# PSU_v1.net
KiCad netlist of a schematic drawn in EAGLE
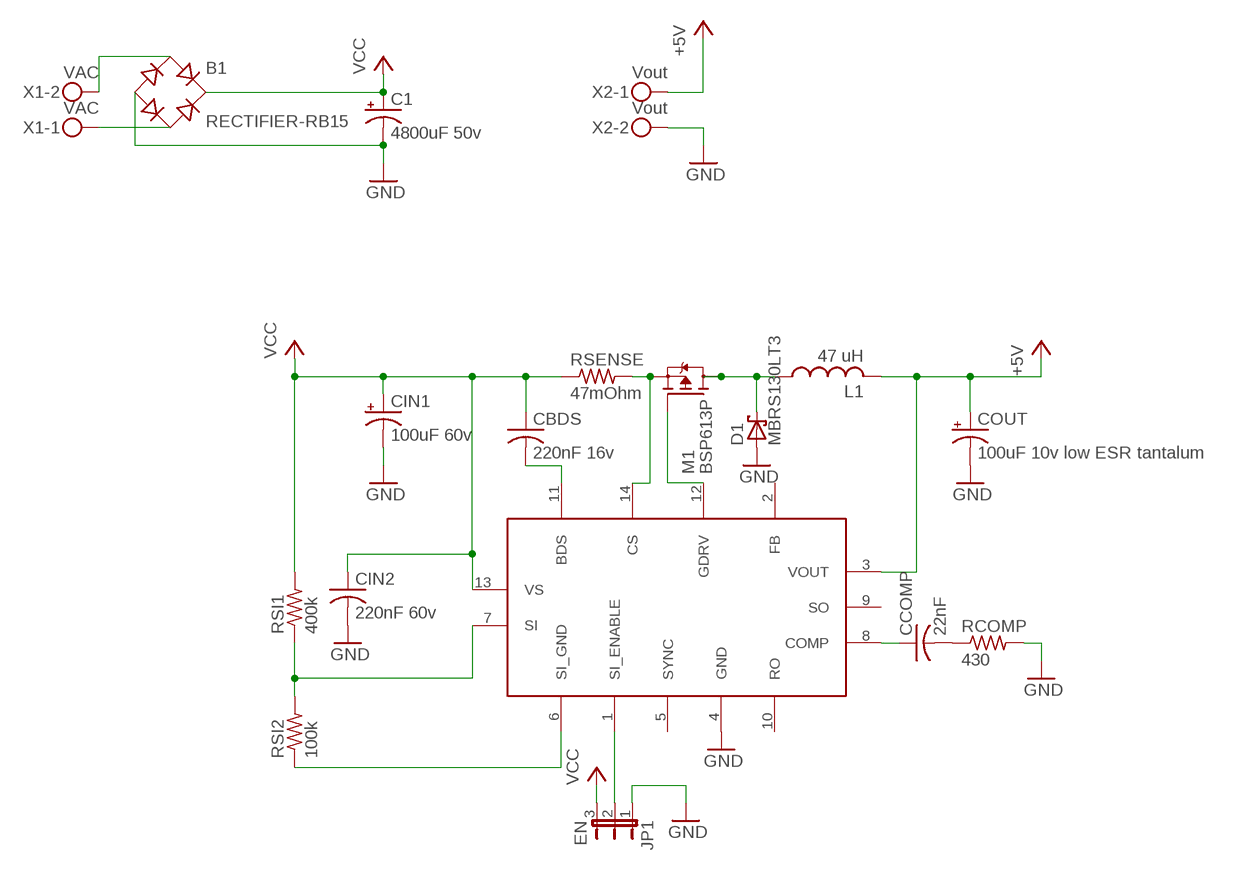
[diagram p0: schematic, sheet 1]

(export (version "E")
  (design (tool "Eeschema 10.0.6"))
  (components
    (comp (ref "B1")
      (value "RECTIFIER-RB15")
      (footprint "eagle-import:RB15")
      (libsource (lib "eagle-import") (part "RECTIFIER-RB15"))
    )
    (comp (ref "C1")
      (value "4800uF 50v")
      (footprint "eagle-import:E7,5-18")
      (libsource (lib "eagle-import") (part "CPOL-USE7.5-18"))
    )
    (comp (ref "CBDS")
      (value "220nF 16v")
      (footprint "eagle-import:C1206")
      (libsource (lib "eagle-import") (part "C-USC1206"))
    )
    (comp (ref "CCOMP")
      (value "22nF")
      (footprint "eagle-import:C1206")
      (libsource (lib "eagle-import") (part "C-USC1206"))
    )
    (comp (ref "CIN1")
      (value "100uF 60v")
      (footprint "eagle-import:140CLH-1010")
      (libsource (lib "eagle-import") (part "CPOL-US140CLH-1010"))
    )
    (comp (ref "CIN2")
      (value "220nF 60v")
      (footprint "eagle-import:C1206")
      (libsource (lib "eagle-import") (part "C-USC1206"))
    )
    (comp (ref "COUT")
      (value "100uF 10v low ESR tantalum")
      (footprint "eagle-import:D_7343-31R")
      (libsource (lib "eagle-import") (part "CPOL-USD/7343-31R"))
    )
    (comp (ref "D1")
      (value "MBRS130LT3")
      (footprint "eagle-import:SMB")
      (libsource (lib "eagle-import") (part "MBRS130LT3"))
    )
    (comp (ref "IC1")
      (value "IFX80471SKV50")
      (footprint "eagle-import:PG-DSO-14")
      (libsource (lib "eagle-import") (part "IFX80471SKV50"))
    )
    (comp (ref "JP1")
      (value "EN")
      (footprint "eagle-import:JP2")
      (libsource (lib "eagle-import") (part "JP2E"))
    )
    (comp (ref "L1")
      (value "47 uH")
      (footprint "eagle-import:SRN6045TA")
      (libsource (lib "eagle-import") (part "L-USSRN6045TA"))
    )
    (comp (ref "M1")
      (value "BSP613P")
      (footprint "eagle-import:PG-SOT-223")
      (libsource (lib "eagle-import") (part "BSP613P"))
    )
    (comp (ref "RCOMP")
      (value "430")
      (footprint "eagle-import:R1206")
      (libsource (lib "eagle-import") (part "R-US_R1206"))
    )
    (comp (ref "RSENSE")
      (value "47mOhm")
      (footprint "eagle-import:R2512")
      (libsource (lib "eagle-import") (part "R-US_R2512"))
    )
    (comp (ref "RSI1")
      (value "400k")
      (footprint "eagle-import:R1206")
      (libsource (lib "eagle-import") (part "R-US_R1206"))
    )
    (comp (ref "RSI2")
      (value "100k")
      (footprint "eagle-import:R1206")
      (libsource (lib "eagle-import") (part "R-US_R1206"))
    )
    (comp (ref "X1")
      (value "VAC")
      (footprint "eagle-import:MKDSN1,5_2-5,08")
      (libsource (lib "eagle-import") (part "MKDSN1,5/2-5,08"))
    )
    (comp (ref "X2")
      (value "Vout")
      (footprint "eagle-import:MKDSN1,5_2-5,08")
      (libsource (lib "eagle-import") (part "MKDSN1,5/2-5,08"))
    )
  )
  (nets
    (net (code "1") (name "+5V") (class "Default")
      (node (ref "COUT") (pin "+") (pinfunction "+_+") (pintype "passive"))
      (node (ref "IC1") (pin "3") (pinfunction "VOUT_3") (pintype "bidirectional"))
      (node (ref "L1") (pin "P$2") (pinfunction "2_P$2") (pintype "passive"))
      (node (ref "X2") (pin "1") (pinfunction "KL_1") (pintype "passive"))
    )
    (net (code "2") (name "GND") (class "Default")
      (node (ref "B1") (pin "-") (pinfunction "-_-") (pintype "passive"))
      (node (ref "C1") (pin "-") (pinfunction "-_-") (pintype "passive"))
      (node (ref "CIN1") (pin "-") (pinfunction "-_-") (pintype "passive"))
      (node (ref "CIN2") (pin "2") (pinfunction "2_2") (pintype "passive"))
      (node (ref "COUT") (pin "-") (pinfunction "-_-") (pintype "passive"))
      (node (ref "D1") (pin "A") (pinfunction "A_A") (pintype "passive"))
      (node (ref "IC1") (pin "4") (pinfunction "GND_4") (pintype "bidirectional"))
      (node (ref "JP1") (pin "1") (pinfunction "1_1") (pintype "passive"))
      (node (ref "RCOMP") (pin "2") (pinfunction "2_2") (pintype "passive"))
      (node (ref "X2") (pin "2") (pinfunction "KL_2") (pintype "passive"))
    )
    (net (code "3") (name "Net-(CCOMP-Pad2)") (class "Default")
      (node (ref "CCOMP") (pin "2") (pinfunction "2_2") (pintype "passive"))
      (node (ref "RCOMP") (pin "1") (pinfunction "1_1") (pintype "passive"))
    )
    (net (code "4") (name "Net-(IC1-BDS)") (class "Default")
      (node (ref "CBDS") (pin "2") (pinfunction "2_2") (pintype "passive"))
      (node (ref "IC1") (pin "11") (pinfunction "BDS_11") (pintype "bidirectional"))
    )
    (net (code "5") (name "Net-(IC1-COMP)") (class "Default")
      (node (ref "CCOMP") (pin "1") (pinfunction "1_1") (pintype "passive"))
      (node (ref "IC1") (pin "8") (pinfunction "COMP_8") (pintype "bidirectional"))
    )
    (net (code "6") (name "Net-(IC1-CS)") (class "Default")
      (node (ref "IC1") (pin "14") (pinfunction "CS_14") (pintype "bidirectional"))
      (node (ref "M1") (pin "3") (pinfunction "S_3") (pintype "passive"))
      (node (ref "RSENSE") (pin "2") (pinfunction "2_2") (pintype "passive"))
    )
    (net (code "7") (name "Net-(IC1-GDRV)") (class "Default")
      (node (ref "IC1") (pin "12") (pinfunction "GDRV_12") (pintype "bidirectional"))
      (node (ref "M1") (pin "1") (pinfunction "G_1") (pintype "passive"))
    )
    (net (code "8") (name "Net-(IC1-SI)") (class "Default")
      (node (ref "IC1") (pin "7") (pinfunction "SI_7") (pintype "bidirectional"))
      (node (ref "RSI1") (pin "1") (pinfunction "1_1") (pintype "passive"))
      (node (ref "RSI2") (pin "2") (pinfunction "2_2") (pintype "passive"))
    )
    (net (code "9") (name "Net-(IC1-SI_ENABLE)") (class "Default")
      (node (ref "IC1") (pin "1") (pinfunction "SI_ENABLE_1") (pintype "bidirectional"))
      (node (ref "JP1") (pin "2") (pinfunction "2_2") (pintype "passive"))
    )
    (net (code "10") (name "Net-(IC1-SI_GND)") (class "Default")
      (node (ref "IC1") (pin "6") (pinfunction "SI_GND_6") (pintype "bidirectional"))
      (node (ref "RSI2") (pin "1") (pinfunction "1_1") (pintype "passive"))
    )
    (net (code "11") (name "Net-(L1-1)") (class "Default")
      (node (ref "D1") (pin "C") (pinfunction "C_C") (pintype "passive"))
      (node (ref "L1") (pin "P$1") (pinfunction "1_P$1") (pintype "passive"))
      (node (ref "M1") (pin "2") (pinfunction "D_2") (pintype "passive"))
      (node (ref "M1") (pin "4") (pinfunction "D_4") (pintype "passive"))
    )
    (net (code "12") (name "Net-(X1A-KL)") (class "Default")
      (node (ref "B1") (pin "AC2") (pinfunction "AC2_AC2") (pintype "passive"))
      (node (ref "X1") (pin "1") (pinfunction "KL_1") (pintype "passive"))
    )
    (net (code "13") (name "Net-(X1B-KL)") (class "Default")
      (node (ref "B1") (pin "AC1") (pinfunction "AC1_AC1") (pintype "passive"))
      (node (ref "X1") (pin "2") (pinfunction "KL_2") (pintype "passive"))
    )
    (net (code "14") (name "VCC") (class "Default")
      (node (ref "B1") (pin "+") (pinfunction "+_+") (pintype "passive"))
      (node (ref "C1") (pin "+") (pinfunction "+_+") (pintype "passive"))
      (node (ref "CBDS") (pin "1") (pinfunction "1_1") (pintype "passive"))
      (node (ref "CIN1") (pin "+") (pinfunction "+_+") (pintype "passive"))
      (node (ref "CIN2") (pin "1") (pinfunction "1_1") (pintype "passive"))
      (node (ref "IC1") (pin "13") (pinfunction "VS_13") (pintype "bidirectional"))
      (node (ref "JP1") (pin "3") (pinfunction "3_3") (pintype "passive"))
      (node (ref "RSENSE") (pin "1") (pinfunction "1_1") (pintype "passive"))
      (node (ref "RSI1") (pin "2") (pinfunction "2_2") (pintype "passive"))
    )
    (net (code "15") (name "unconnected-(IC1-FB-Pad2)") (class "Default")
      (node (ref "IC1") (pin "2") (pinfunction "FB_2") (pintype "bidirectional"))
    )
    (net (code "16") (name "unconnected-(IC1-RO-Pad10)") (class "Default")
      (node (ref "IC1") (pin "10") (pinfunction "RO_10") (pintype "bidirectional"))
    )
    (net (code "17") (name "unconnected-(IC1-SO-Pad9)") (class "Default")
      (node (ref "IC1") (pin "9") (pinfunction "SO_9") (pintype "bidirectional"))
    )
    (net (code "18") (name "unconnected-(IC1-SYNC-Pad5)") (class "Default")
      (node (ref "IC1") (pin "5") (pinfunction "SYNC_5") (pintype "bidirectional"))
    )
  )
)
